# USB.net
KiCad netlist of a schematic drawn in Altium Designer
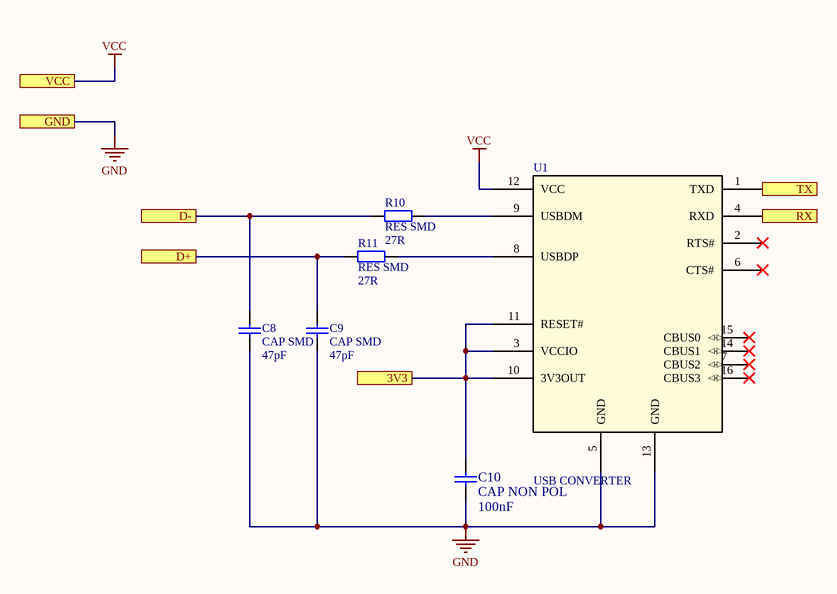
[diagram p0: USB.SchDoc]

(export (version "E")
  (design (tool "Eeschema 10.0.6"))
  (components
    (comp (ref "C8")
      (value "CAP SMD")
      (footprint "CAP SMD")
      (description "Capacitor (Semiconductor SIM Model)")
      (fields (field (name "ALTIUM_VALUE") "47pF") (field (name "PUBLISHER") "Altium Limited"))
      (libsource (lib "MySchem") (part "CONDENSADOR SMD"))
    )
    (comp (ref "C9")
      (value "CAP SMD")
      (footprint "CAP SMD")
      (description "Capacitor (Semiconductor SIM Model)")
      (fields (field (name "ALTIUM_VALUE") "47pF") (field (name "PUBLISHER") "Altium Limited"))
      (libsource (lib "MySchem") (part "CONDENSADOR SMD"))
    )
    (comp (ref "C10")
      (value "CAP NON POL")
      (footprint "Capacitor 100nF")
      (description "Capacitor")
      (fields (field (name "ALTIUM_VALUE") "100nF") (field (name "PUBLISHER") "Altium Limited"))
      (libsource (lib "MySchem") (part "Cap"))
    )
    (comp (ref "R10")
      (value "RES SMD")
      (footprint "RES SMDD")
      (description "Resistor")
      (fields (field (name "ALTIUM_VALUE") "27R") (field (name "PUBLISHER") "Altium Limited"))
      (libsource (lib "MySchem") (part "RES SMD"))
    )
    (comp (ref "R11")
      (value "RES SMD")
      (footprint "RES SMDD")
      (description "Resistor")
      (fields (field (name "ALTIUM_VALUE") "27R") (field (name "PUBLISHER") "Altium Limited"))
      (libsource (lib "MySchem") (part "RES SMD"))
    )
    (comp (ref "U1")
      (value "USB CONVERTER")
      (footprint "CONVERSOR USB PARA UART")
      (description "No Description Available")
      (fields
        (field (name "MANUFACTURER_PART_NUMBER") "FT230XS-R")
        (field (name "COPYRIGHT") "Copyright (C) 2023 Ultra Librarian. All rights reserved.")
      )
      (libsource (lib "FT230XS-R") (part "FT230XS-R"))
    )
  )
  (nets
    (net (code "1") (name "/3V3") (class "Default")
      (node (ref "C10") (pin "2") (pinfunction "2_2") (pintype "passive"))
      (node (ref "U1") (pin "10") (pinfunction "3V3OUT_10") (pintype "passive"))
      (node (ref "U1") (pin "11") (pinfunction "RESET#_11") (pintype "passive"))
      (node (ref "U1") (pin "3") (pinfunction "VCCIO_3") (pintype "power_in"))
    )
    (net (code "2") (name "/D+") (class "Default")
      (node (ref "C9") (pin "1") (pinfunction "1_1") (pintype "passive"))
      (node (ref "R11") (pin "1") (pinfunction "1_1") (pintype "passive"))
    )
    (net (code "3") (name "/D-") (class "Default")
      (node (ref "C8") (pin "1") (pinfunction "1_1") (pintype "passive"))
      (node (ref "R10") (pin "1") (pinfunction "1_1") (pintype "passive"))
    )
    (net (code "4") (name "/RX") (class "Default")
      (node (ref "U1") (pin "4") (pinfunction "RXD_4") (pintype "passive"))
    )
    (net (code "5") (name "/TX") (class "Default")
      (node (ref "U1") (pin "1") (pinfunction "TXD_1") (pintype "passive"))
    )
    (net (code "6") (name "GND") (class "Default")
      (node (ref "C10") (pin "1") (pinfunction "1_1") (pintype "passive"))
      (node (ref "C8") (pin "2") (pinfunction "2_2") (pintype "passive"))
      (node (ref "C9") (pin "2") (pinfunction "2_2") (pintype "passive"))
      (node (ref "U1") (pin "13") (pinfunction "GND_13") (pintype "power_in"))
      (node (ref "U1") (pin "5") (pinfunction "GND_5") (pintype "power_in"))
    )
    (net (code "7") (name "Net-(U1-USBDM)") (class "Default")
      (node (ref "R10") (pin "2") (pinfunction "2_2") (pintype "passive"))
      (node (ref "U1") (pin "9") (pinfunction "USBDM_9") (pintype "passive"))
    )
    (net (code "8") (name "Net-(U1-USBDP)") (class "Default")
      (node (ref "R11") (pin "2") (pinfunction "2_2") (pintype "passive"))
      (node (ref "U1") (pin "8") (pinfunction "USBDP_8") (pintype "passive"))
    )
    (net (code "9") (name "VCC") (class "Default")
      (node (ref "U1") (pin "12") (pinfunction "VCC_12") (pintype "power_in"))
    )
    (net (code "10") (name "unconnected-(U1-CBUS0-Pad15)") (class "Default")
      (node (ref "U1") (pin "15") (pinfunction "CBUS0_15") (pintype "bidirectional+no_connect"))
    )
    (net (code "11") (name "unconnected-(U1-CBUS1-Pad14)") (class "Default")
      (node (ref "U1") (pin "14") (pinfunction "CBUS1_14") (pintype "bidirectional+no_connect"))
    )
    (net (code "12") (name "unconnected-(U1-CBUS2-Pad7)") (class "Default")
      (node (ref "U1") (pin "7") (pinfunction "CBUS2_7") (pintype "bidirectional+no_connect"))
    )
    (net (code "13") (name "unconnected-(U1-CBUS3-Pad16)") (class "Default")
      (node (ref "U1") (pin "16") (pinfunction "CBUS3_16") (pintype "bidirectional+no_connect"))
    )
    (net (code "14") (name "unconnected-(U1-CTS#-Pad6)") (class "Default")
      (node (ref "U1") (pin "6") (pinfunction "CTS#_6") (pintype "passive+no_connect"))
    )
    (net (code "15") (name "unconnected-(U1-RTS#-Pad2)") (class "Default")
      (node (ref "U1") (pin "2") (pinfunction "RTS#_2") (pintype "passive+no_connect"))
    )
  )
)
